# MQ_GasSensors_Board.net
KiCad netlist of a schematic drawn in EAGLE
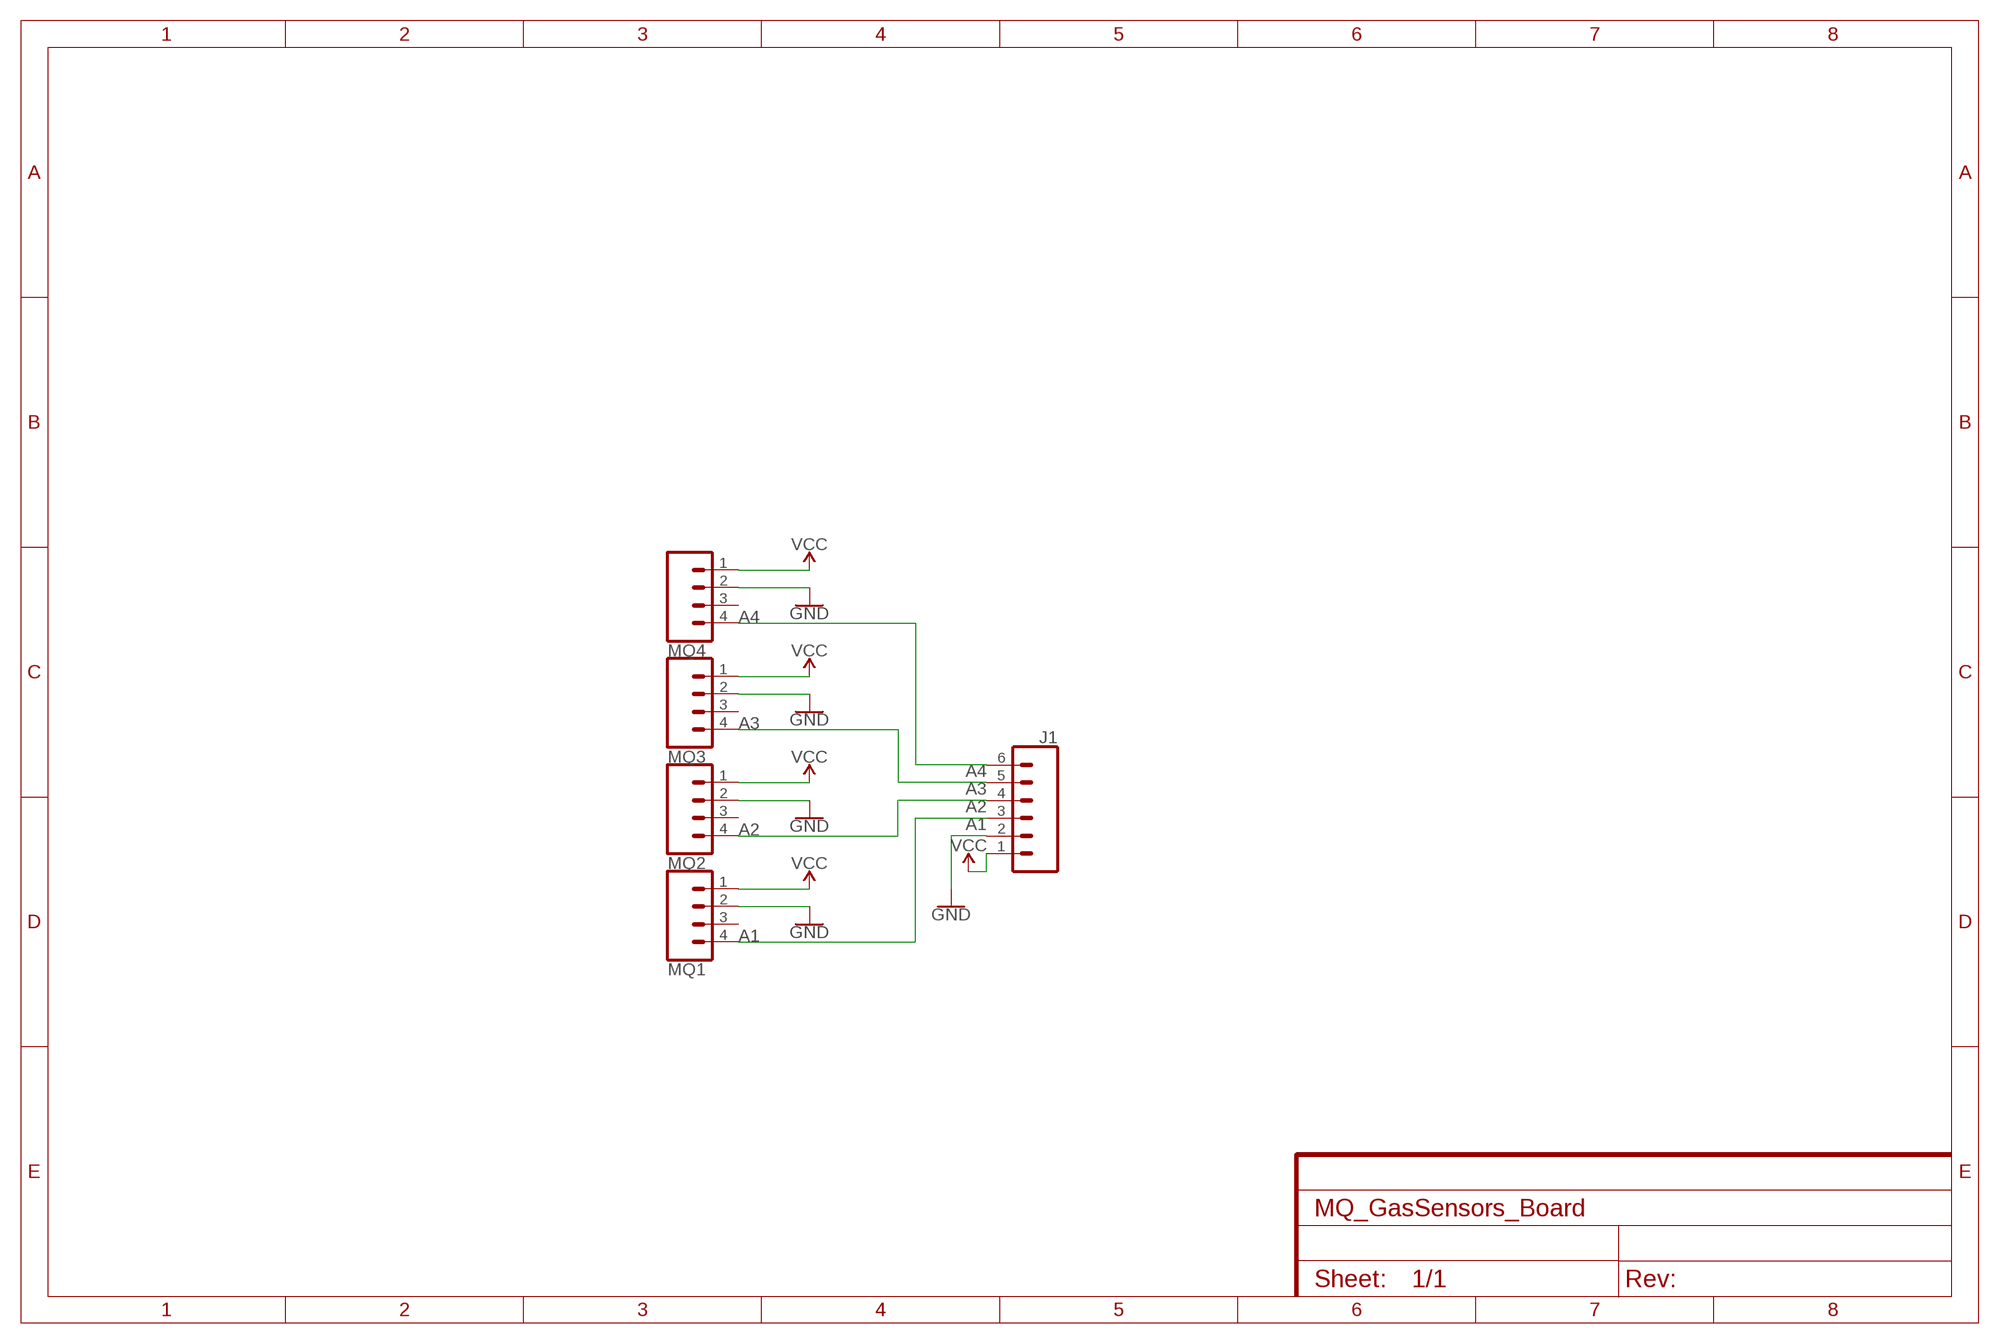
[diagram p0: schematic, sheet 1]

(export (version "E")
  (design (tool "Eeschema 10.0.6"))
  (components
    (comp (ref "J1")
      (value "CONN_06SILK_FEMALE_PTH")
      (footprint "eagle-import:1X06")
      (libsource (lib "eagle-import") (part "CONN_06SILK_FEMALE_PTH"))
    )
    (comp (ref "MQ1")
      (value "CONN_04")
      (footprint "eagle-import:1X04")
      (libsource (lib "eagle-import") (part "CONN_04"))
    )
    (comp (ref "MQ2")
      (value "CONN_04")
      (footprint "eagle-import:1X04")
      (libsource (lib "eagle-import") (part "CONN_04"))
    )
    (comp (ref "MQ3")
      (value "CONN_04")
      (footprint "eagle-import:1X04")
      (libsource (lib "eagle-import") (part "CONN_04"))
    )
    (comp (ref "MQ4")
      (value "CONN_04")
      (footprint "eagle-import:1X04")
      (libsource (lib "eagle-import") (part "CONN_04"))
    )
  )
  (nets
    (net (code "1") (name "/A1") (class "Default")
      (node (ref "J1") (pin "3") (pinfunction "3_3") (pintype "passive"))
      (node (ref "MQ1") (pin "4") (pinfunction "4_4") (pintype "passive"))
    )
    (net (code "2") (name "/A2") (class "Default")
      (node (ref "J1") (pin "4") (pinfunction "4_4") (pintype "passive"))
      (node (ref "MQ2") (pin "4") (pinfunction "4_4") (pintype "passive"))
    )
    (net (code "3") (name "/A3") (class "Default")
      (node (ref "J1") (pin "5") (pinfunction "5_5") (pintype "passive"))
      (node (ref "MQ3") (pin "4") (pinfunction "4_4") (pintype "passive"))
    )
    (net (code "4") (name "/A4") (class "Default")
      (node (ref "J1") (pin "6") (pinfunction "6_6") (pintype "passive"))
      (node (ref "MQ4") (pin "4") (pinfunction "4_4") (pintype "passive"))
    )
    (net (code "5") (name "GND") (class "Default")
      (node (ref "J1") (pin "2") (pinfunction "2_2") (pintype "passive"))
      (node (ref "MQ1") (pin "2") (pinfunction "2_2") (pintype "passive"))
      (node (ref "MQ2") (pin "2") (pinfunction "2_2") (pintype "passive"))
      (node (ref "MQ3") (pin "2") (pinfunction "2_2") (pintype "passive"))
      (node (ref "MQ4") (pin "2") (pinfunction "2_2") (pintype "passive"))
    )
    (net (code "6") (name "VCC") (class "Default")
      (node (ref "J1") (pin "1") (pinfunction "1_1") (pintype "passive"))
      (node (ref "MQ1") (pin "1") (pinfunction "1_1") (pintype "passive"))
      (node (ref "MQ2") (pin "1") (pinfunction "1_1") (pintype "passive"))
      (node (ref "MQ3") (pin "1") (pinfunction "1_1") (pintype "passive"))
      (node (ref "MQ4") (pin "1") (pinfunction "1_1") (pintype "passive"))
    )
    (net (code "7") (name "unconnected-(MQ1-Pad3)") (class "Default")
      (node (ref "MQ1") (pin "3") (pinfunction "3_3") (pintype "passive"))
    )
    (net (code "8") (name "unconnected-(MQ2-Pad3)") (class "Default")
      (node (ref "MQ2") (pin "3") (pinfunction "3_3") (pintype "passive"))
    )
    (net (code "9") (name "unconnected-(MQ3-Pad3)") (class "Default")
      (node (ref "MQ3") (pin "3") (pinfunction "3_3") (pintype "passive"))
    )
    (net (code "10") (name "unconnected-(MQ4-Pad3)") (class "Default")
      (node (ref "MQ4") (pin "3") (pinfunction "3_3") (pintype "passive"))
    )
  )
)
